# LDR-1.net
KiCad netlist of a schematic drawn in EAGLE
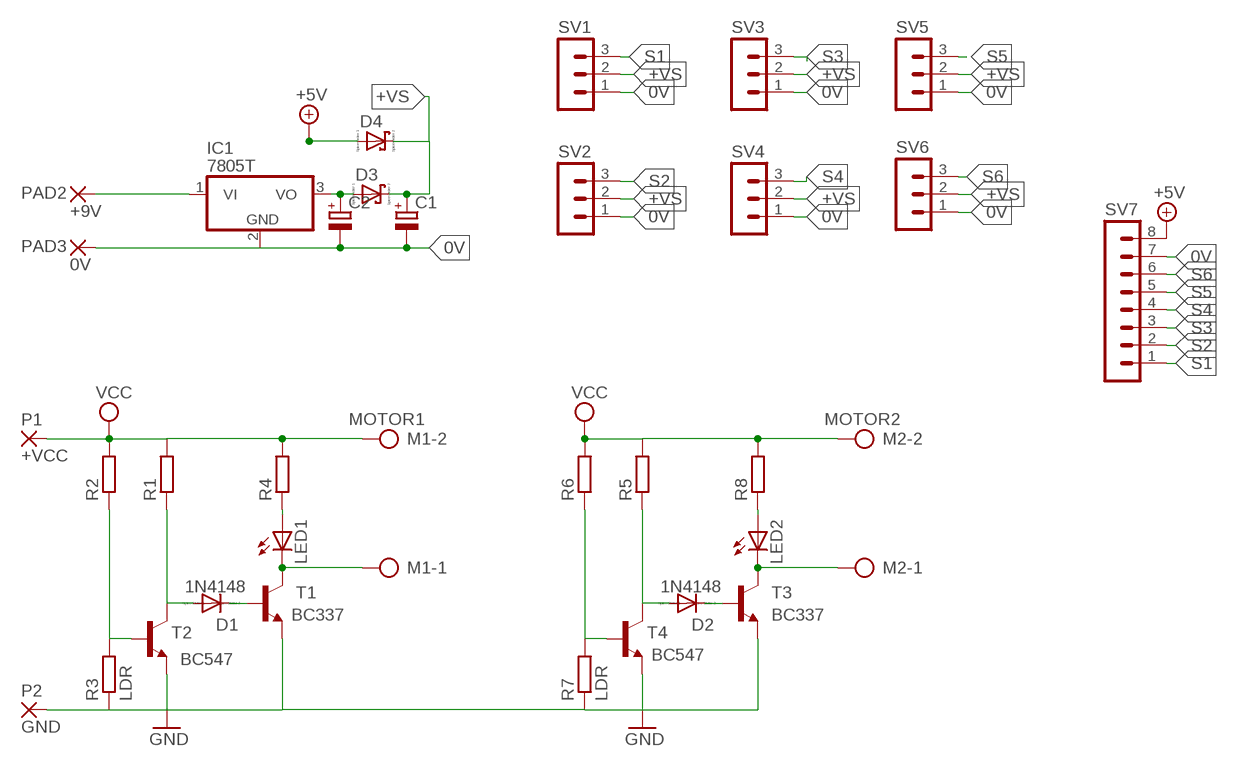
[diagram p0: schematic, sheet 1]

(export (version "E")
  (design (tool "Eeschema 10.0.6"))
  (components
    (comp (ref "C1")
      (value "CPOL-EUE2.5-5")
      (footprint "eagle-import:E2,5-5")
      (libsource (lib "eagle-import") (part "CPOL-EUE2.5-5"))
    )
    (comp (ref "C2")
      (value "CPOL-EUE2.5-5")
      (footprint "eagle-import:E2,5-5")
      (libsource (lib "eagle-import") (part "CPOL-EUE2.5-5"))
    )
    (comp (ref "D1")
      (value "1N4148")
      (footprint "eagle-import:DO35-7")
      (libsource (lib "eagle-import") (part "1N4148DO35-7"))
    )
    (comp (ref "D2")
      (value "1N4148")
      (footprint "eagle-import:DO35-7")
      (libsource (lib "eagle-import") (part "1N4148DO35-7"))
    )
    (comp (ref "D3")
      (value "SCHOTTKY-DIODEDO35-7")
      (footprint "eagle-import:DIODE_DO35-7")
      (libsource (lib "eagle-import") (part "SCHOTTKY-DIODEDO35-7"))
    )
    (comp (ref "D4")
      (value "SCHOTTKY-DIODEDO35-7")
      (footprint "eagle-import:DIODE_DO35-7")
      (libsource (lib "eagle-import") (part "SCHOTTKY-DIODEDO35-7"))
    )
    (comp (ref "IC1")
      (value "7805T")
      (footprint "eagle-import:TO220H")
      (libsource (lib "eagle-import") (part "78T05"))
    )
    (comp (ref "LED1")
      (value "LED3MM")
      (footprint "eagle-import:LED3MM")
      (libsource (lib "eagle-import") (part "LED3MM"))
    )
    (comp (ref "LED2")
      (value "LED3MM")
      (footprint "eagle-import:LED3MM")
      (libsource (lib "eagle-import") (part "LED3MM"))
    )
    (comp (ref "M1")
      (value "MOTOR1")
      (footprint "eagle-import:AK500_2")
      (libsource (lib "eagle-import") (part "AK500/2"))
    )
    (comp (ref "M2")
      (value "MOTOR2")
      (footprint "eagle-import:AK500_2")
      (libsource (lib "eagle-import") (part "AK500/2"))
    )
    (comp (ref "P1")
      (value "+VCC")
      (footprint "eagle-import:2,15_1,0")
      (libsource (lib "eagle-import") (part "WIREPAD2,15/1,0"))
    )
    (comp (ref "P2")
      (value "GND")
      (footprint "eagle-import:2,15_1,0")
      (libsource (lib "eagle-import") (part "WIREPAD2,15/1,0"))
    )
    (comp (ref "PAD2")
      (value "+9V")
      (footprint "eagle-import:2,15_1,0")
      (libsource (lib "eagle-import") (part "WIREPAD2,15/1,0"))
    )
    (comp (ref "PAD3")
      (value "0V")
      (footprint "eagle-import:2,15_1,0")
      (libsource (lib "eagle-import") (part "WIREPAD2,15/1,0"))
    )
    (comp (ref "R1")
      (value "R-EU_0207/7")
      (footprint "eagle-import:0207_7")
      (libsource (lib "eagle-import") (part "R-EU_0207/7"))
    )
    (comp (ref "R2")
      (value "R-EU_0207/7")
      (footprint "eagle-import:0207_7")
      (libsource (lib "eagle-import") (part "R-EU_0207/7"))
    )
    (comp (ref "R3")
      (value "LDR")
      (footprint "eagle-import:0204_5")
      (libsource (lib "eagle-import") (part "R-EU_0204/5"))
    )
    (comp (ref "R4")
      (value "R-EU_0207/7")
      (footprint "eagle-import:0207_7")
      (libsource (lib "eagle-import") (part "R-EU_0207/7"))
    )
    (comp (ref "R5")
      (value "R-EU_0207/7")
      (footprint "eagle-import:0207_7")
      (libsource (lib "eagle-import") (part "R-EU_0207/7"))
    )
    (comp (ref "R6")
      (value "R-EU_0207/7")
      (footprint "eagle-import:0207_7")
      (libsource (lib "eagle-import") (part "R-EU_0207/7"))
    )
    (comp (ref "R7")
      (value "LDR")
      (footprint "eagle-import:0204_5")
      (libsource (lib "eagle-import") (part "R-EU_0204/5"))
    )
    (comp (ref "R8")
      (value "R-EU_0207/7")
      (footprint "eagle-import:0207_7")
      (libsource (lib "eagle-import") (part "R-EU_0207/7"))
    )
    (comp (ref "SV1")
      (value "MA03-1")
      (footprint "eagle-import:MA03-1")
      (libsource (lib "eagle-import") (part "MA03-1"))
    )
    (comp (ref "SV2")
      (value "MA03-1")
      (footprint "eagle-import:MA03-1")
      (libsource (lib "eagle-import") (part "MA03-1"))
    )
    (comp (ref "SV3")
      (value "MA03-1")
      (footprint "eagle-import:MA03-1")
      (libsource (lib "eagle-import") (part "MA03-1"))
    )
    (comp (ref "SV4")
      (value "MA03-1")
      (footprint "eagle-import:MA03-1")
      (libsource (lib "eagle-import") (part "MA03-1"))
    )
    (comp (ref "SV5")
      (value "MA03-1")
      (footprint "eagle-import:MA03-1")
      (libsource (lib "eagle-import") (part "MA03-1"))
    )
    (comp (ref "SV6")
      (value "MA03-1")
      (footprint "eagle-import:MA03-1")
      (libsource (lib "eagle-import") (part "MA03-1"))
    )
    (comp (ref "SV7")
      (value "MA08-1")
      (footprint "eagle-import:MA08-1")
      (libsource (lib "eagle-import") (part "MA08-1"))
    )
    (comp (ref "T1")
      (value "BC337")
      (footprint "eagle-import:TO92-CBE")
      (libsource (lib "eagle-import") (part "-NPN-TO92-CBEBC337-25"))
    )
    (comp (ref "T2")
      (value "BC547")
      (footprint "eagle-import:TO92-CBE")
      (libsource (lib "eagle-import") (part "-NPN-TO92-CBEBC547"))
    )
    (comp (ref "T3")
      (value "BC337")
      (footprint "eagle-import:TO92-CBE")
      (libsource (lib "eagle-import") (part "-NPN-TO92-CBEBC337-25"))
    )
    (comp (ref "T4")
      (value "BC547")
      (footprint "eagle-import:TO92-CBE")
      (libsource (lib "eagle-import") (part "-NPN-TO92-CBEBC547"))
    )
  )
  (nets
    (net (code "1") (name "+5V") (class "Default")
      (node (ref "D4") (pin "A") (pinfunction "C_A") (pintype "passive"))
      (node (ref "SV7") (pin "8") (pinfunction "8_8") (pintype "passive"))
    )
    (net (code "2") (name "+VS") (class "Default")
      (node (ref "C1") (pin "+") (pinfunction "+_+") (pintype "passive"))
      (node (ref "D3") (pin "C") (pinfunction "A_C") (pintype "passive"))
      (node (ref "D4") (pin "C") (pinfunction "A_C") (pintype "passive"))
      (node (ref "SV1") (pin "2") (pinfunction "2_2") (pintype "passive"))
      (node (ref "SV2") (pin "2") (pinfunction "2_2") (pintype "passive"))
      (node (ref "SV3") (pin "2") (pinfunction "2_2") (pintype "passive"))
      (node (ref "SV4") (pin "2") (pinfunction "2_2") (pintype "passive"))
      (node (ref "SV5") (pin "2") (pinfunction "2_2") (pintype "passive"))
      (node (ref "SV6") (pin "2") (pinfunction "2_2") (pintype "passive"))
    )
    (net (code "3") (name "0V") (class "Default")
      (node (ref "C1") (pin "-") (pinfunction "-_-") (pintype "passive"))
      (node (ref "C2") (pin "-") (pinfunction "-_-") (pintype "passive"))
      (node (ref "IC1") (pin "2") (pinfunction "GND_2") (pintype "passive"))
      (node (ref "PAD3") (pin "1") (pinfunction "P_1") (pintype "passive"))
      (node (ref "SV1") (pin "1") (pinfunction "1_1") (pintype "passive"))
      (node (ref "SV2") (pin "1") (pinfunction "1_1") (pintype "passive"))
      (node (ref "SV3") (pin "1") (pinfunction "1_1") (pintype "passive"))
      (node (ref "SV4") (pin "1") (pinfunction "1_1") (pintype "passive"))
      (node (ref "SV5") (pin "1") (pinfunction "1_1") (pintype "passive"))
      (node (ref "SV6") (pin "1") (pinfunction "1_1") (pintype "passive"))
      (node (ref "SV7") (pin "7") (pinfunction "7_7") (pintype "passive"))
    )
    (net (code "4") (name "GND") (class "Default")
      (node (ref "P2") (pin "1") (pinfunction "P_1") (pintype "passive"))
      (node (ref "R3") (pin "1") (pinfunction "1_1") (pintype "passive"))
      (node (ref "R7") (pin "1") (pinfunction "1_1") (pintype "passive"))
      (node (ref "T1") (pin "E") (pinfunction "E_E") (pintype "passive"))
      (node (ref "T2") (pin "E") (pinfunction "E_E") (pintype "passive"))
      (node (ref "T3") (pin "E") (pinfunction "E_E") (pintype "passive"))
      (node (ref "T4") (pin "E") (pinfunction "E_E") (pintype "passive"))
    )
    (net (code "5") (name "Net-(D1-PadA)") (class "Default")
      (node (ref "D1") (pin "A") (pinfunction "A_A") (pintype "passive"))
      (node (ref "R1") (pin "1") (pinfunction "1_1") (pintype "passive"))
      (node (ref "T2") (pin "C") (pinfunction "C_C") (pintype "passive"))
    )
    (net (code "6") (name "Net-(D1-PadC)") (class "Default")
      (node (ref "D1") (pin "C") (pinfunction "C_C") (pintype "passive"))
      (node (ref "T1") (pin "B") (pinfunction "B_B") (pintype "passive"))
    )
    (net (code "7") (name "Net-(D2-PadA)") (class "Default")
      (node (ref "D2") (pin "A") (pinfunction "A_A") (pintype "passive"))
      (node (ref "R5") (pin "1") (pinfunction "1_1") (pintype "passive"))
      (node (ref "T4") (pin "C") (pinfunction "C_C") (pintype "passive"))
    )
    (net (code "8") (name "Net-(D2-PadC)") (class "Default")
      (node (ref "D2") (pin "C") (pinfunction "C_C") (pintype "passive"))
      (node (ref "T3") (pin "B") (pinfunction "B_B") (pintype "passive"))
    )
    (net (code "9") (name "Net-(D3-C)") (class "Default")
      (node (ref "C2") (pin "+") (pinfunction "+_+") (pintype "passive"))
      (node (ref "D3") (pin "A") (pinfunction "C_A") (pintype "passive"))
      (node (ref "IC1") (pin "3") (pinfunction "VO_3") (pintype "passive"))
    )
    (net (code "10") (name "Net-(IC1-VI)") (class "Default")
      (node (ref "IC1") (pin "1") (pinfunction "VI_1") (pintype "input"))
      (node (ref "PAD2") (pin "1") (pinfunction "P_1") (pintype "passive"))
    )
    (net (code "11") (name "Net-(LED1-C)") (class "Default")
      (node (ref "LED1") (pin "K") (pinfunction "C_K") (pintype "passive"))
      (node (ref "M1") (pin "1") (pinfunction "KL_1") (pintype "passive"))
      (node (ref "T1") (pin "C") (pinfunction "C_C") (pintype "passive"))
    )
    (net (code "12") (name "Net-(LED1-PadA)") (class "Default")
      (node (ref "LED1") (pin "A") (pinfunction "A_A") (pintype "passive"))
      (node (ref "R4") (pin "1") (pinfunction "1_1") (pintype "passive"))
    )
    (net (code "13") (name "Net-(LED2-C)") (class "Default")
      (node (ref "LED2") (pin "K") (pinfunction "C_K") (pintype "passive"))
      (node (ref "M2") (pin "1") (pinfunction "KL_1") (pintype "passive"))
      (node (ref "T3") (pin "C") (pinfunction "C_C") (pintype "passive"))
    )
    (net (code "14") (name "Net-(LED2-PadA)") (class "Default")
      (node (ref "LED2") (pin "A") (pinfunction "A_A") (pintype "passive"))
      (node (ref "R8") (pin "1") (pinfunction "1_1") (pintype "passive"))
    )
    (net (code "15") (name "Net-(R2-Pad1)") (class "Default")
      (node (ref "R2") (pin "1") (pinfunction "1_1") (pintype "passive"))
      (node (ref "R3") (pin "2") (pinfunction "2_2") (pintype "passive"))
      (node (ref "T2") (pin "B") (pinfunction "B_B") (pintype "passive"))
    )
    (net (code "16") (name "Net-(R6-Pad1)") (class "Default")
      (node (ref "R6") (pin "1") (pinfunction "1_1") (pintype "passive"))
      (node (ref "R7") (pin "2") (pinfunction "2_2") (pintype "passive"))
      (node (ref "T4") (pin "B") (pinfunction "B_B") (pintype "passive"))
    )
    (net (code "17") (name "S1") (class "Default")
      (node (ref "SV1") (pin "3") (pinfunction "3_3") (pintype "passive"))
      (node (ref "SV7") (pin "1") (pinfunction "1_1") (pintype "passive"))
    )
    (net (code "18") (name "S2") (class "Default")
      (node (ref "SV2") (pin "3") (pinfunction "3_3") (pintype "passive"))
      (node (ref "SV7") (pin "2") (pinfunction "2_2") (pintype "passive"))
    )
    (net (code "19") (name "S3") (class "Default")
      (node (ref "SV3") (pin "3") (pinfunction "3_3") (pintype "passive"))
      (node (ref "SV7") (pin "3") (pinfunction "3_3") (pintype "passive"))
    )
    (net (code "20") (name "S4") (class "Default")
      (node (ref "SV4") (pin "3") (pinfunction "3_3") (pintype "passive"))
      (node (ref "SV7") (pin "4") (pinfunction "4_4") (pintype "passive"))
    )
    (net (code "21") (name "S5") (class "Default")
      (node (ref "SV5") (pin "3") (pinfunction "3_3") (pintype "passive"))
      (node (ref "SV7") (pin "5") (pinfunction "5_5") (pintype "passive"))
    )
    (net (code "22") (name "S6") (class "Default")
      (node (ref "SV6") (pin "3") (pinfunction "3_3") (pintype "passive"))
      (node (ref "SV7") (pin "6") (pinfunction "6_6") (pintype "passive"))
    )
    (net (code "23") (name "VCC") (class "Default")
      (node (ref "M1") (pin "2") (pinfunction "KL_2") (pintype "passive"))
      (node (ref "M2") (pin "2") (pinfunction "KL_2") (pintype "passive"))
      (node (ref "P1") (pin "1") (pinfunction "P_1") (pintype "passive"))
      (node (ref "R1") (pin "2") (pinfunction "2_2") (pintype "passive"))
      (node (ref "R2") (pin "2") (pinfunction "2_2") (pintype "passive"))
      (node (ref "R4") (pin "2") (pinfunction "2_2") (pintype "passive"))
      (node (ref "R5") (pin "2") (pinfunction "2_2") (pintype "passive"))
      (node (ref "R6") (pin "2") (pinfunction "2_2") (pintype "passive"))
      (node (ref "R8") (pin "2") (pinfunction "2_2") (pintype "passive"))
    )
  )
)
